# CTR-Dome-Rev-A-Leds-1.net
KiCad netlist of a schematic drawn in Altium Designer
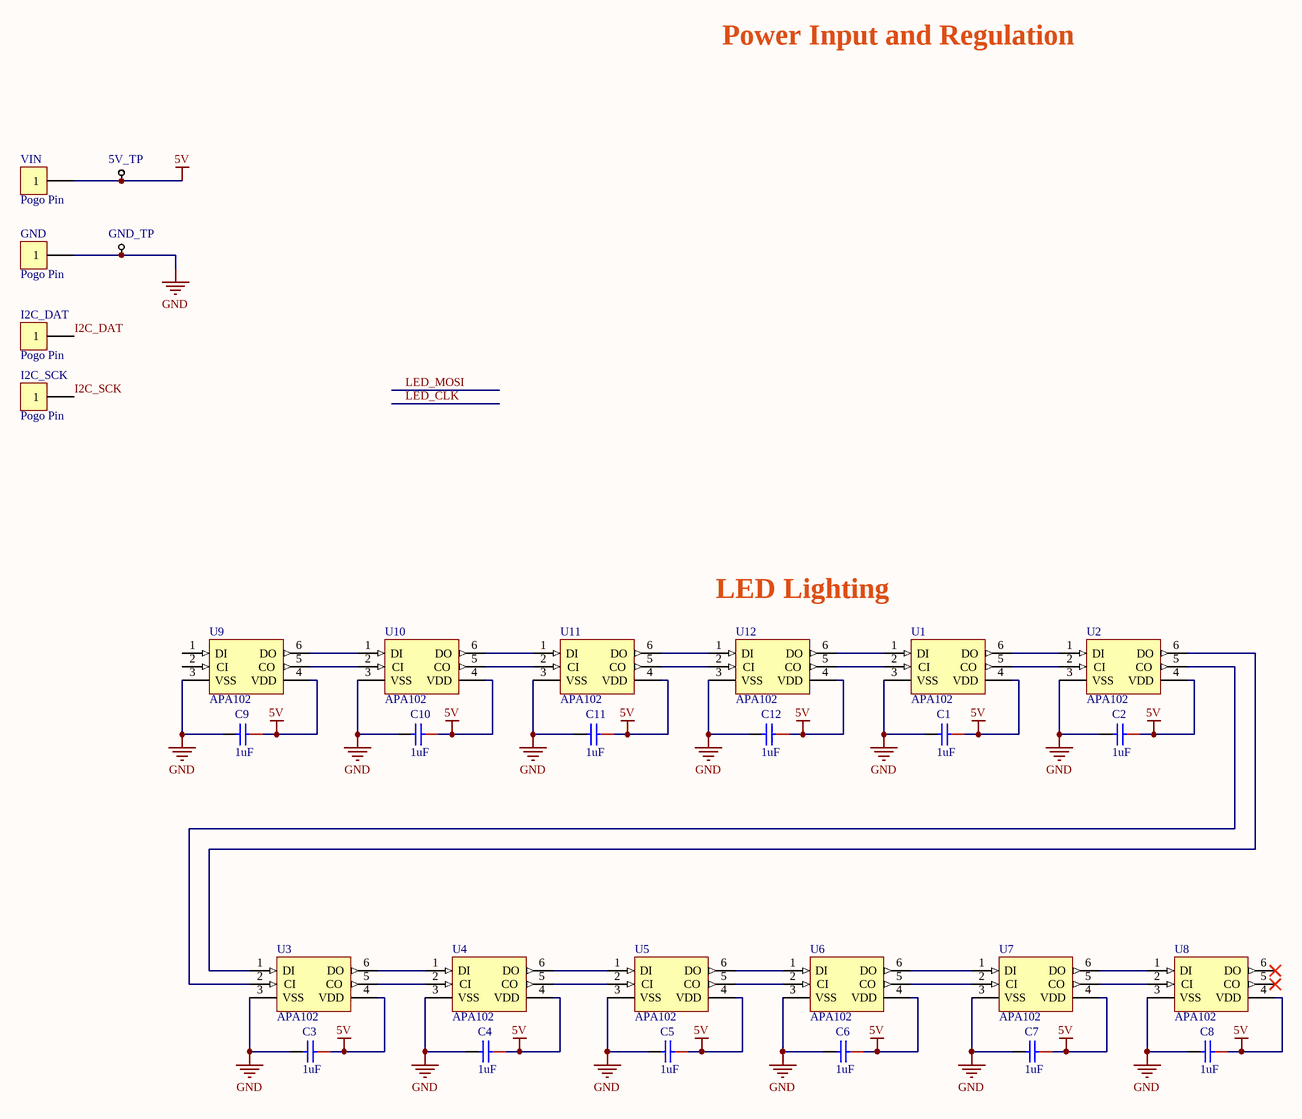
[diagram p0: CTR-Dome-Rev-A-Leds-1.SchDoc]

(export (version "E")
  (design (tool "Eeschema 10.0.6"))
  (components
    (comp (ref "5V_TP")
      (value "Test Point")
      (footprint "TestPoint-TH 42 mil")
      (libsource (lib "OLogic-Misc") (part "TestPoint, small"))
    )
    (comp (ref "C1")
      (value "1uF")
      (footprint "CAPC0402(1005)_N")
      (description "1UF 0402")
      (fields
        (field (name "MANUFACTURER") "TDK Corporation")
        (field (name "MANUFACTURER PART NUMBER") "C1005X5R1C105K050BC")
      )
      (libsource (lib "OLogic-Passive") (part "CAP CER 1UF 16V 10% X5R 0402"))
    )
    (comp (ref "C2")
      (value "1uF")
      (footprint "CAPC0402(1005)_N")
      (description "1UF 0402")
      (fields
        (field (name "MANUFACTURER") "TDK Corporation")
        (field (name "MANUFACTURER PART NUMBER") "C1005X5R1C105K050BC")
      )
      (libsource (lib "OLogic-Passive") (part "CAP CER 1UF 16V 10% X5R 0402"))
    )
    (comp (ref "C3")
      (value "1uF")
      (footprint "CAPC0402(1005)_N")
      (description "1UF 0402")
      (fields
        (field (name "MANUFACTURER") "TDK Corporation")
        (field (name "MANUFACTURER PART NUMBER") "C1005X5R1C105K050BC")
      )
      (libsource (lib "OLogic-Passive") (part "CAP CER 1UF 16V 10% X5R 0402"))
    )
    (comp (ref "C4")
      (value "1uF")
      (footprint "CAPC0402(1005)_N")
      (description "1UF 0402")
      (fields
        (field (name "MANUFACTURER") "TDK Corporation")
        (field (name "MANUFACTURER PART NUMBER") "C1005X5R1C105K050BC")
      )
      (libsource (lib "OLogic-Passive") (part "CAP CER 1UF 16V 10% X5R 0402"))
    )
    (comp (ref "C5")
      (value "1uF")
      (footprint "CAPC0402(1005)_N")
      (description "1UF 0402")
      (fields
        (field (name "MANUFACTURER") "TDK Corporation")
        (field (name "MANUFACTURER PART NUMBER") "C1005X5R1C105K050BC")
      )
      (libsource (lib "OLogic-Passive") (part "CAP CER 1UF 16V 10% X5R 0402"))
    )
    (comp (ref "C6")
      (value "1uF")
      (footprint "CAPC0402(1005)_N")
      (description "1UF 0402")
      (fields
        (field (name "MANUFACTURER") "TDK Corporation")
        (field (name "MANUFACTURER PART NUMBER") "C1005X5R1C105K050BC")
      )
      (libsource (lib "OLogic-Passive") (part "CAP CER 1UF 16V 10% X5R 0402"))
    )
    (comp (ref "C7")
      (value "1uF")
      (footprint "CAPC0402(1005)_N")
      (description "1UF 0402")
      (fields
        (field (name "MANUFACTURER") "TDK Corporation")
        (field (name "MANUFACTURER PART NUMBER") "C1005X5R1C105K050BC")
      )
      (libsource (lib "OLogic-Passive") (part "CAP CER 1UF 16V 10% X5R 0402"))
    )
    (comp (ref "C8")
      (value "1uF")
      (footprint "CAPC0402(1005)_N")
      (description "1UF 0402")
      (fields
        (field (name "MANUFACTURER") "TDK Corporation")
        (field (name "MANUFACTURER PART NUMBER") "C1005X5R1C105K050BC")
      )
      (libsource (lib "OLogic-Passive") (part "CAP CER 1UF 16V 10% X5R 0402"))
    )
    (comp (ref "C9")
      (value "1uF")
      (footprint "CAPC0402(1005)_N")
      (description "1UF 0402")
      (fields
        (field (name "MANUFACTURER") "TDK Corporation")
        (field (name "MANUFACTURER PART NUMBER") "C1005X5R1C105K050BC")
      )
      (libsource (lib "OLogic-Passive") (part "CAP CER 1UF 16V 10% X5R 0402"))
    )
    (comp (ref "C10")
      (value "1uF")
      (footprint "CAPC0402(1005)_N")
      (description "1UF 0402")
      (fields
        (field (name "MANUFACTURER") "TDK Corporation")
        (field (name "MANUFACTURER PART NUMBER") "C1005X5R1C105K050BC")
      )
      (libsource (lib "OLogic-Passive") (part "CAP CER 1UF 16V 10% X5R 0402"))
    )
    (comp (ref "C11")
      (value "1uF")
      (footprint "CAPC0402(1005)_N")
      (description "1UF 0402")
      (fields
        (field (name "MANUFACTURER") "TDK Corporation")
        (field (name "MANUFACTURER PART NUMBER") "C1005X5R1C105K050BC")
      )
      (libsource (lib "OLogic-Passive") (part "CAP CER 1UF 16V 10% X5R 0402"))
    )
    (comp (ref "C12")
      (value "1uF")
      (footprint "CAPC0402(1005)_N")
      (description "1UF 0402")
      (fields
        (field (name "MANUFACTURER") "TDK Corporation")
        (field (name "MANUFACTURER PART NUMBER") "C1005X5R1C105K050BC")
      )
      (libsource (lib "OLogic-Passive") (part "CAP CER 1UF 16V 10% X5R 0402"))
    )
    (comp (ref "GND")
      (value "Pogo Pin")
      (footprint "POGO_PIN")
      (fields
        (field (name "MANUFACTURER") "Mill-Max Manufacturing Corp.")
        (field (name "MANUFACTURER PART NUMBER") "0850-0-15-20-83-14-11-0")
      )
      (libsource (lib "OLogic-Connectors") (part "0850-0-15-20-83-14-11-0"))
    )
    (comp (ref "GND_TP")
      (value "Test Point")
      (footprint "TestPoint-TH 42 mil")
      (libsource (lib "OLogic-Misc") (part "TestPoint, small"))
    )
    (comp (ref "I2C_DAT")
      (value "Pogo Pin")
      (footprint "POGO_PIN")
      (fields
        (field (name "MANUFACTURER") "Mill-Max Manufacturing Corp.")
        (field (name "MANUFACTURER PART NUMBER") "0850-0-15-20-83-14-11-0")
      )
      (libsource (lib "OLogic-Connectors") (part "0850-0-15-20-83-14-11-0"))
    )
    (comp (ref "I2C_SCK")
      (value "Pogo Pin")
      (footprint "POGO_PIN")
      (fields
        (field (name "MANUFACTURER") "Mill-Max Manufacturing Corp.")
        (field (name "MANUFACTURER PART NUMBER") "0850-0-15-20-83-14-11-0")
      )
      (libsource (lib "OLogic-Connectors") (part "0850-0-15-20-83-14-11-0"))
    )
    (comp (ref "U1")
      (value "APA102")
      (footprint "APA102C")
      (description "APA102 RGB LED with serial controller")
      (fields (field (name "MANUFACTURER") "Shiji Lighting") (field (name "MPN") "APA102C"))
      (libsource (lib "OLogic-Diode-Opto-LED") (part "APA102"))
    )
    (comp (ref "U2")
      (value "APA102")
      (footprint "APA102C")
      (description "APA102 RGB LED with serial controller")
      (fields (field (name "MANUFACTURER") "Shiji Lighting") (field (name "MPN") "APA102C"))
      (libsource (lib "OLogic-Diode-Opto-LED") (part "APA102"))
    )
    (comp (ref "U3")
      (value "APA102")
      (footprint "APA102C")
      (description "APA102 RGB LED with serial controller")
      (fields (field (name "MANUFACTURER") "Shiji Lighting") (field (name "MPN") "APA102C"))
      (libsource (lib "OLogic-Diode-Opto-LED") (part "APA102"))
    )
    (comp (ref "U4")
      (value "APA102")
      (footprint "APA102C")
      (description "APA102 RGB LED with serial controller")
      (fields (field (name "MANUFACTURER") "Shiji Lighting") (field (name "MPN") "APA102C"))
      (libsource (lib "OLogic-Diode-Opto-LED") (part "APA102"))
    )
    (comp (ref "U5")
      (value "APA102")
      (footprint "APA102C")
      (description "APA102 RGB LED with serial controller")
      (fields (field (name "MANUFACTURER") "Shiji Lighting") (field (name "MPN") "APA102C"))
      (libsource (lib "OLogic-Diode-Opto-LED") (part "APA102"))
    )
    (comp (ref "U6")
      (value "APA102")
      (footprint "APA102C")
      (description "APA102 RGB LED with serial controller")
      (fields (field (name "MANUFACTURER") "Shiji Lighting") (field (name "MPN") "APA102C"))
      (libsource (lib "OLogic-Diode-Opto-LED") (part "APA102"))
    )
    (comp (ref "U7")
      (value "APA102")
      (footprint "APA102C")
      (description "APA102 RGB LED with serial controller")
      (fields (field (name "MANUFACTURER") "Shiji Lighting") (field (name "MPN") "APA102C"))
      (libsource (lib "OLogic-Diode-Opto-LED") (part "APA102"))
    )
    (comp (ref "U8")
      (value "APA102")
      (footprint "APA102C")
      (description "APA102 RGB LED with serial controller")
      (fields (field (name "MANUFACTURER") "Shiji Lighting") (field (name "MPN") "APA102C"))
      (libsource (lib "OLogic-Diode-Opto-LED") (part "APA102"))
    )
    (comp (ref "U9")
      (value "APA102")
      (footprint "APA102C")
      (description "APA102 RGB LED with serial controller")
      (fields (field (name "MANUFACTURER") "Shiji Lighting") (field (name "MPN") "APA102C"))
      (libsource (lib "OLogic-Diode-Opto-LED") (part "APA102"))
    )
    (comp (ref "U10")
      (value "APA102")
      (footprint "APA102C")
      (description "APA102 RGB LED with serial controller")
      (fields (field (name "MANUFACTURER") "Shiji Lighting") (field (name "MPN") "APA102C"))
      (libsource (lib "OLogic-Diode-Opto-LED") (part "APA102"))
    )
    (comp (ref "U11")
      (value "APA102")
      (footprint "APA102C")
      (description "APA102 RGB LED with serial controller")
      (fields (field (name "MANUFACTURER") "Shiji Lighting") (field (name "MPN") "APA102C"))
      (libsource (lib "OLogic-Diode-Opto-LED") (part "APA102"))
    )
    (comp (ref "U12")
      (value "APA102")
      (footprint "APA102C")
      (description "APA102 RGB LED with serial controller")
      (fields (field (name "MANUFACTURER") "Shiji Lighting") (field (name "MPN") "APA102C"))
      (libsource (lib "OLogic-Diode-Opto-LED") (part "APA102"))
    )
    (comp (ref "VIN")
      (value "Pogo Pin")
      (footprint "POGO_PIN")
      (fields
        (field (name "MANUFACTURER") "Mill-Max Manufacturing Corp.")
        (field (name "MANUFACTURER PART NUMBER") "0850-0-15-20-83-14-11-0")
      )
      (libsource (lib "OLogic-Connectors") (part "0850-0-15-20-83-14-11-0"))
    )
  )
  (nets
    (net (code "1") (name "/I2C_DAT") (class "Default")
      (node (ref "I2C_DAT") (pin "1") (pinfunction "1_1") (pintype "passive"))
    )
    (net (code "2") (name "/I2C_SCK") (class "Default")
      (node (ref "I2C_SCK") (pin "1") (pinfunction "1_1") (pintype "passive"))
    )
    (net (code "5") (name "5V") (class "Default")
      (node (ref "5V_TP") (pin "1") (pinfunction "1_1") (pintype "passive"))
      (node (ref "C1") (pin "1") (pinfunction "1_1") (pintype "passive"))
      (node (ref "C10") (pin "1") (pinfunction "1_1") (pintype "passive"))
      (node (ref "C11") (pin "1") (pinfunction "1_1") (pintype "passive"))
      (node (ref "C12") (pin "1") (pinfunction "1_1") (pintype "passive"))
      (node (ref "C2") (pin "1") (pinfunction "1_1") (pintype "passive"))
      (node (ref "C3") (pin "1") (pinfunction "1_1") (pintype "passive"))
      (node (ref "C4") (pin "1") (pinfunction "1_1") (pintype "passive"))
      (node (ref "C5") (pin "1") (pinfunction "1_1") (pintype "passive"))
      (node (ref "C6") (pin "1") (pinfunction "1_1") (pintype "passive"))
      (node (ref "C7") (pin "1") (pinfunction "1_1") (pintype "passive"))
      (node (ref "C8") (pin "1") (pinfunction "1_1") (pintype "passive"))
      (node (ref "C9") (pin "1") (pinfunction "1_1") (pintype "passive"))
      (node (ref "U1") (pin "4") (pinfunction "VDD_4") (pintype "power_in"))
      (node (ref "U10") (pin "4") (pinfunction "VDD_4") (pintype "power_in"))
      (node (ref "U11") (pin "4") (pinfunction "VDD_4") (pintype "power_in"))
      (node (ref "U12") (pin "4") (pinfunction "VDD_4") (pintype "power_in"))
      (node (ref "U2") (pin "4") (pinfunction "VDD_4") (pintype "power_in"))
      (node (ref "U3") (pin "4") (pinfunction "VDD_4") (pintype "power_in"))
      (node (ref "U4") (pin "4") (pinfunction "VDD_4") (pintype "power_in"))
      (node (ref "U5") (pin "4") (pinfunction "VDD_4") (pintype "power_in"))
      (node (ref "U6") (pin "4") (pinfunction "VDD_4") (pintype "power_in"))
      (node (ref "U7") (pin "4") (pinfunction "VDD_4") (pintype "power_in"))
      (node (ref "U8") (pin "4") (pinfunction "VDD_4") (pintype "power_in"))
      (node (ref "U9") (pin "4") (pinfunction "VDD_4") (pintype "power_in"))
      (node (ref "VIN") (pin "1") (pinfunction "1_1") (pintype "passive"))
    )
    (net (code "6") (name "GND") (class "Default")
      (node (ref "C1") (pin "2") (pinfunction "2_2") (pintype "passive"))
      (node (ref "C10") (pin "2") (pinfunction "2_2") (pintype "passive"))
      (node (ref "C11") (pin "2") (pinfunction "2_2") (pintype "passive"))
      (node (ref "C12") (pin "2") (pinfunction "2_2") (pintype "passive"))
      (node (ref "C2") (pin "2") (pinfunction "2_2") (pintype "passive"))
      (node (ref "C3") (pin "2") (pinfunction "2_2") (pintype "passive"))
      (node (ref "C4") (pin "2") (pinfunction "2_2") (pintype "passive"))
      (node (ref "C5") (pin "2") (pinfunction "2_2") (pintype "passive"))
      (node (ref "C6") (pin "2") (pinfunction "2_2") (pintype "passive"))
      (node (ref "C7") (pin "2") (pinfunction "2_2") (pintype "passive"))
      (node (ref "C8") (pin "2") (pinfunction "2_2") (pintype "passive"))
      (node (ref "C9") (pin "2") (pinfunction "2_2") (pintype "passive"))
      (node (ref "GND") (pin "1") (pinfunction "1_1") (pintype "passive"))
      (node (ref "GND_TP") (pin "1") (pinfunction "1_1") (pintype "passive"))
      (node (ref "U1") (pin "3") (pinfunction "VSS_3") (pintype "power_in"))
      (node (ref "U10") (pin "3") (pinfunction "VSS_3") (pintype "power_in"))
      (node (ref "U11") (pin "3") (pinfunction "VSS_3") (pintype "power_in"))
      (node (ref "U12") (pin "3") (pinfunction "VSS_3") (pintype "power_in"))
      (node (ref "U2") (pin "3") (pinfunction "VSS_3") (pintype "power_in"))
      (node (ref "U3") (pin "3") (pinfunction "VSS_3") (pintype "power_in"))
      (node (ref "U4") (pin "3") (pinfunction "VSS_3") (pintype "power_in"))
      (node (ref "U5") (pin "3") (pinfunction "VSS_3") (pintype "power_in"))
      (node (ref "U6") (pin "3") (pinfunction "VSS_3") (pintype "power_in"))
      (node (ref "U7") (pin "3") (pinfunction "VSS_3") (pintype "power_in"))
      (node (ref "U8") (pin "3") (pinfunction "VSS_3") (pintype "power_in"))
      (node (ref "U9") (pin "3") (pinfunction "VSS_3") (pintype "power_in"))
    )
    (net (code "7") (name "Net-(U1-CI)") (class "Default")
      (node (ref "U1") (pin "2") (pinfunction "CI_2") (pintype "input"))
      (node (ref "U12") (pin "5") (pinfunction "CO_5") (pintype "output"))
    )
    (net (code "8") (name "Net-(U1-CO)") (class "Default")
      (node (ref "U1") (pin "5") (pinfunction "CO_5") (pintype "output"))
      (node (ref "U2") (pin "2") (pinfunction "CI_2") (pintype "input"))
    )
    (net (code "9") (name "Net-(U1-DI)") (class "Default")
      (node (ref "U1") (pin "1") (pinfunction "DI_1") (pintype "input"))
      (node (ref "U12") (pin "6") (pinfunction "DO_6") (pintype "output"))
    )
    (net (code "10") (name "Net-(U1-DO)") (class "Default")
      (node (ref "U1") (pin "6") (pinfunction "DO_6") (pintype "output"))
      (node (ref "U2") (pin "1") (pinfunction "DI_1") (pintype "input"))
    )
    (net (code "11") (name "Net-(U2-CO)") (class "Default")
      (node (ref "U2") (pin "5") (pinfunction "CO_5") (pintype "output"))
      (node (ref "U3") (pin "2") (pinfunction "CI_2") (pintype "input"))
    )
    (net (code "12") (name "Net-(U2-DO)") (class "Default")
      (node (ref "U2") (pin "6") (pinfunction "DO_6") (pintype "output"))
      (node (ref "U3") (pin "1") (pinfunction "DI_1") (pintype "input"))
    )
    (net (code "13") (name "Net-(U3-CO)") (class "Default")
      (node (ref "U3") (pin "5") (pinfunction "CO_5") (pintype "output"))
      (node (ref "U4") (pin "2") (pinfunction "CI_2") (pintype "input"))
    )
    (net (code "14") (name "Net-(U3-DO)") (class "Default")
      (node (ref "U3") (pin "6") (pinfunction "DO_6") (pintype "output"))
      (node (ref "U4") (pin "1") (pinfunction "DI_1") (pintype "input"))
    )
    (net (code "15") (name "Net-(U4-CO)") (class "Default")
      (node (ref "U4") (pin "5") (pinfunction "CO_5") (pintype "output"))
      (node (ref "U5") (pin "2") (pinfunction "CI_2") (pintype "input"))
    )
    (net (code "16") (name "Net-(U4-DO)") (class "Default")
      (node (ref "U4") (pin "6") (pinfunction "DO_6") (pintype "output"))
      (node (ref "U5") (pin "1") (pinfunction "DI_1") (pintype "input"))
    )
    (net (code "17") (name "Net-(U5-CO)") (class "Default")
      (node (ref "U5") (pin "5") (pinfunction "CO_5") (pintype "output"))
      (node (ref "U6") (pin "2") (pinfunction "CI_2") (pintype "input"))
    )
    (net (code "18") (name "Net-(U5-DO)") (class "Default")
      (node (ref "U5") (pin "6") (pinfunction "DO_6") (pintype "output"))
      (node (ref "U6") (pin "1") (pinfunction "DI_1") (pintype "input"))
    )
    (net (code "19") (name "Net-(U6-CO)") (class "Default")
      (node (ref "U6") (pin "5") (pinfunction "CO_5") (pintype "output"))
      (node (ref "U7") (pin "2") (pinfunction "CI_2") (pintype "input"))
    )
    (net (code "20") (name "Net-(U6-DO)") (class "Default")
      (node (ref "U6") (pin "6") (pinfunction "DO_6") (pintype "output"))
      (node (ref "U7") (pin "1") (pinfunction "DI_1") (pintype "input"))
    )
    (net (code "21") (name "Net-(U7-CO)") (class "Default")
      (node (ref "U7") (pin "5") (pinfunction "CO_5") (pintype "output"))
      (node (ref "U8") (pin "2") (pinfunction "CI_2") (pintype "input"))
    )
    (net (code "22") (name "Net-(U7-DO)") (class "Default")
      (node (ref "U7") (pin "6") (pinfunction "DO_6") (pintype "output"))
      (node (ref "U8") (pin "1") (pinfunction "DI_1") (pintype "input"))
    )
    (net (code "23") (name "Net-(U10-CI)") (class "Default")
      (node (ref "U10") (pin "2") (pinfunction "CI_2") (pintype "input"))
      (node (ref "U9") (pin "5") (pinfunction "CO_5") (pintype "output"))
    )
    (net (code "24") (name "Net-(U10-CO)") (class "Default")
      (node (ref "U10") (pin "5") (pinfunction "CO_5") (pintype "output"))
      (node (ref "U11") (pin "2") (pinfunction "CI_2") (pintype "input"))
    )
    (net (code "25") (name "Net-(U10-DI)") (class "Default")
      (node (ref "U10") (pin "1") (pinfunction "DI_1") (pintype "input"))
      (node (ref "U9") (pin "6") (pinfunction "DO_6") (pintype "output"))
    )
    (net (code "26") (name "Net-(U10-DO)") (class "Default")
      (node (ref "U10") (pin "6") (pinfunction "DO_6") (pintype "output"))
      (node (ref "U11") (pin "1") (pinfunction "DI_1") (pintype "input"))
    )
    (net (code "27") (name "Net-(U11-CO)") (class "Default")
      (node (ref "U11") (pin "5") (pinfunction "CO_5") (pintype "output"))
      (node (ref "U12") (pin "2") (pinfunction "CI_2") (pintype "input"))
    )
    (net (code "28") (name "Net-(U11-DO)") (class "Default")
      (node (ref "U11") (pin "6") (pinfunction "DO_6") (pintype "output"))
      (node (ref "U12") (pin "1") (pinfunction "DI_1") (pintype "input"))
    )
    (net (code "29") (name "unconnected-(U8-CO-Pad5)") (class "Default")
      (node (ref "U8") (pin "5") (pinfunction "CO_5") (pintype "output+no_connect"))
    )
    (net (code "30") (name "unconnected-(U8-DO-Pad6)") (class "Default")
      (node (ref "U8") (pin "6") (pinfunction "DO_6") (pintype "output+no_connect"))
    )
    (net (code "31") (name "unconnected-(U9-CI-Pad2)") (class "Default")
      (node (ref "U9") (pin "2") (pinfunction "CI_2") (pintype "input"))
    )
    (net (code "32") (name "unconnected-(U9-DI-Pad1)") (class "Default")
      (node (ref "U9") (pin "1") (pinfunction "DI_1") (pintype "input"))
    )
  )
)
